# USB_OTG.net
KiCad netlist of a schematic drawn in Altium Designer
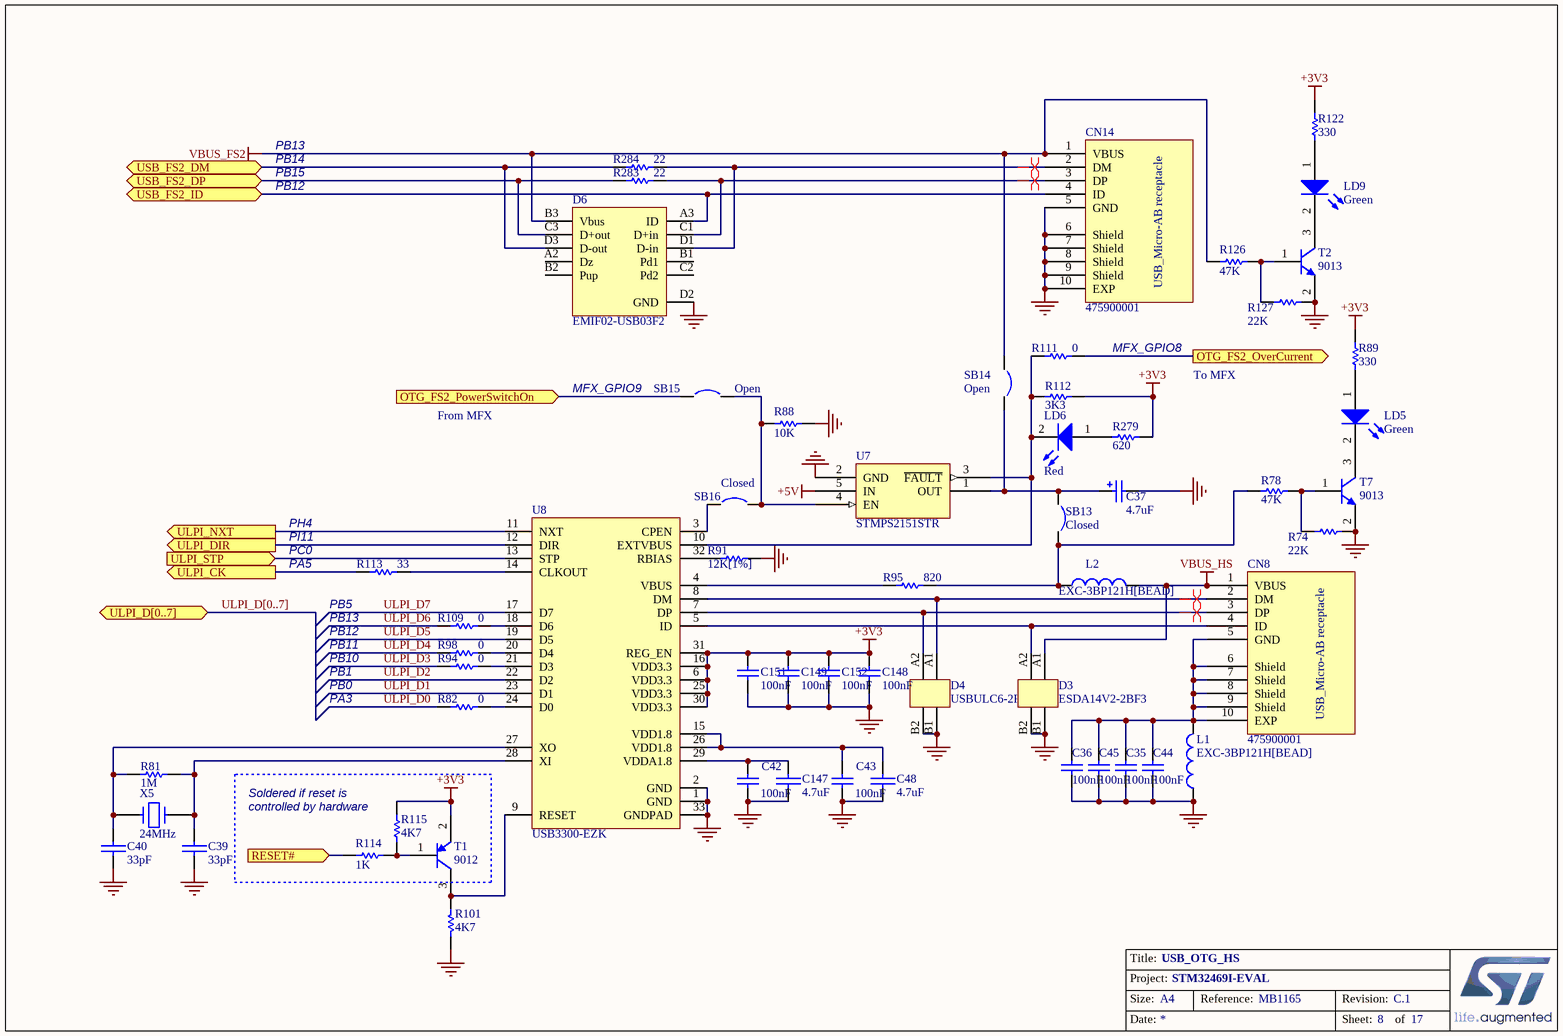
[diagram p0: USB_OTG.SchDoc]

(export (version "E")
  (design (tool "Eeschema 10.0.6"))
  (components
    (comp (ref "C35")
      (value "100nF")
      (footprint "0603C")
      (description "Capacitor")
      (fields (field (name "PUBLISHER") "Altium Limited"))
      (libsource (lib "Miscellaneous Devices") (part "Cap"))
    )
    (comp (ref "C36")
      (value "100nF")
      (footprint "0603C")
      (description "Capacitor")
      (fields (field (name "PUBLISHER") "Altium Limited"))
      (libsource (lib "Miscellaneous Devices") (part "Cap"))
    )
    (comp (ref "C37")
      (value "4.7uF")
      (footprint "TAN-A")
      (description "Polarized Capacitor (Radial)")
      (fields (field (name "PUBLISHER") "Altium Limited"))
      (libsource (lib "Miscellaneous Devices") (part "Cap Pol1"))
    )
    (comp (ref "C39")
      (value "33pF")
      (footprint "0603C")
      (description "Capacitor")
      (libsource (lib "") (part "CAP_1"))
    )
    (comp (ref "C40")
      (value "33pF")
      (footprint "0603C")
      (description "Capacitor")
      (libsource (lib "") (part "CAP_1"))
    )
    (comp (ref "C42")
      (value "100nF")
      (footprint "0603C")
      (description "Capacitor")
      (fields (field (name "PUBLISHER") "Altium Limited"))
      (libsource (lib "Miscellaneous Devices") (part "Cap"))
    )
    (comp (ref "C43")
      (value "100nF")
      (footprint "0603C")
      (description "Capacitor")
      (fields (field (name "PUBLISHER") "Altium Limited"))
      (libsource (lib "Miscellaneous Devices") (part "Cap"))
    )
    (comp (ref "C44")
      (value "100nF")
      (footprint "0603C")
      (description "Capacitor")
      (fields (field (name "PUBLISHER") "Altium Limited"))
      (libsource (lib "Miscellaneous Devices") (part "Cap"))
    )
    (comp (ref "C45")
      (value "100nF")
      (footprint "0603C")
      (description "Capacitor")
      (fields (field (name "PUBLISHER") "Altium Limited"))
      (libsource (lib "Miscellaneous Devices") (part "Cap"))
    )
    (comp (ref "C48")
      (value "4.7uF")
      (footprint "TAN-A")
      (description "Capacitor")
      (libsource (lib "*") (part "CAP"))
    )
    (comp (ref "C147")
      (value "4.7uF")
      (footprint "TAN-A")
      (description "Capacitor")
      (libsource (lib "*") (part "CAP"))
    )
    (comp (ref "C148")
      (value "100nF")
      (footprint "0603C")
      (description "Capacitor")
      (fields (field (name "PUBLISHER") "Altium Limited"))
      (libsource (lib "Miscellaneous Devices") (part "Cap"))
    )
    (comp (ref "C149")
      (value "100nF")
      (footprint "0603C")
      (description "Capacitor")
      (fields (field (name "PUBLISHER") "Altium Limited"))
      (libsource (lib "Miscellaneous Devices") (part "Cap"))
    )
    (comp (ref "C151")
      (value "100nF")
      (footprint "0603C")
      (description "Capacitor")
      (fields (field (name "PUBLISHER") "Altium Limited"))
      (libsource (lib "Miscellaneous Devices") (part "Cap"))
    )
    (comp (ref "C152")
      (value "100nF")
      (footprint "0603C")
      (description "Capacitor")
      (fields (field (name "PUBLISHER") "Altium Limited"))
      (libsource (lib "Miscellaneous Devices") (part "Cap"))
    )
    (comp (ref "CN8")
      (value "475900001")
      (footprint "MOLEX_47590001")
      (libsource (lib "mb1045") (part "475900001"))
    )
    (comp (ref "CN14")
      (value "475900001")
      (footprint "MOLEX_47590001")
      (libsource (lib "mb1045") (part "475900001"))
    )
    (comp (ref "D3")
      (value "ESDA14V2-2BF3")
      (footprint "BGA4_0R4_0R8X0R8")
      (libsource (lib "MB786") (part "ESDA14V2-2BF3"))
    )
    (comp (ref "D4")
      (value "USBULC6-2F3")
      (footprint "BGA4_0R4_1X1")
      (libsource (lib "MB786") (part "USBULC6-2F3"))
    )
    (comp (ref "D6")
      (value "EMIF02-USB03F2")
      (footprint "BGA11_0R5_1R57X2R07")
      (libsource (lib "mb1045") (part "EMIF02-USB03F2"))
    )
    (comp (ref "L1")
      (value "EXC-3BP121H[BEAD]")
      (footprint "0603L")
      (description "Inductor")
      (fields (field (name "PUBLISHER") "Altium Limited"))
      (libsource (lib "Miscellaneous Devices") (part "Inductor"))
    )
    (comp (ref "L2")
      (value "EXC-3BP121H[BEAD]")
      (footprint "0603L")
      (description "Inductor")
      (fields (field (name "PUBLISHER") "Altium Limited"))
      (libsource (lib "Miscellaneous Devices") (part "Inductor"))
    )
    (comp (ref "LD5")
      (value "Green")
      (footprint "0603D")
      (description "Typical RED, GREEN, YELLOW, AMBER GaAs LED")
      (fields (field (name "PUBLISHER") "Altium Limited"))
      (libsource (lib "Miscellaneous Devices") (part "LED2"))
    )
    (comp (ref "LD6")
      (value "Red")
      (footprint "0603D")
      (description "Typical RED, GREEN, YELLOW, AMBER GaAs LED")
      (fields (field (name "PUBLISHER") "Altium Limited"))
      (libsource (lib "Miscellaneous Devices") (part "LED2"))
    )
    (comp (ref "LD9")
      (value "Green")
      (footprint "0603D")
      (description "Typical RED, GREEN, YELLOW, AMBER GaAs LED")
      (fields (field (name "PUBLISHER") "Altium Limited"))
      (libsource (lib "Miscellaneous Devices") (part "LED2"))
    )
    (comp (ref "R74")
      (value "22K")
      (footprint "0603R")
      (description "Resistor")
      (fields (field (name "PUBLISHER") "Altium Limited"))
      (libsource (lib "Miscellaneous Devices") (part "res1"))
    )
    (comp (ref "R78")
      (value "47K")
      (footprint "0603R")
      (description "Resistor")
      (fields (field (name "PUBLISHER") "Altium Limited"))
      (libsource (lib "Miscellaneous Devices") (part "res1"))
    )
    (comp (ref "R81")
      (value "1M")
      (footprint "0603R")
      (description "Resistor")
      (fields (field (name "PUBLISHER") "Altium Limited"))
      (libsource (lib "Miscellaneous Devices") (part "Res1"))
    )
    (comp (ref "R82")
      (value "0")
      (footprint "0603R")
      (description "Resistor")
      (fields (field (name "PUBLISHER") "Altium Limited"))
      (libsource (lib "Miscellaneous Devices") (part "Res1"))
    )
    (comp (ref "R88")
      (value "10K")
      (footprint "0603R")
      (description "Resistor")
      (fields (field (name "PUBLISHER") "Altium Limited"))
      (libsource (lib "Miscellaneous Devices") (part "res1"))
    )
    (comp (ref "R89")
      (value "330")
      (footprint "0603R")
      (description "Resistor")
      (fields (field (name "PUBLISHER") "Altium Limited"))
      (libsource (lib "Miscellaneous Devices") (part "res1"))
    )
    (comp (ref "R91")
      (value "12K[1%]")
      (footprint "0603R")
      (description "Resistor")
      (fields (field (name "PUBLISHER") "Altium Limited"))
      (libsource (lib "Miscellaneous Devices") (part "Res1"))
    )
    (comp (ref "R94")
      (value "0")
      (footprint "0603R")
      (description "Resistor")
      (fields (field (name "PUBLISHER") "Altium Limited"))
      (libsource (lib "Miscellaneous Devices") (part "Res1"))
    )
    (comp (ref "R95")
      (value "820")
      (footprint "0603R")
      (description "Resistor")
      (fields (field (name "PUBLISHER") "Altium Limited"))
      (libsource (lib "Miscellaneous Devices") (part "res1"))
    )
    (comp (ref "R98")
      (value "0")
      (footprint "0603R")
      (description "Resistor")
      (fields (field (name "PUBLISHER") "Altium Limited"))
      (libsource (lib "Miscellaneous Devices") (part "Res1"))
    )
    (comp (ref "R101")
      (value "4K7")
      (footprint "0603R")
      (description "Resistor")
      (fields (field (name "PUBLISHER") "Altium Limited"))
      (libsource (lib "*") (part "Res1"))
    )
    (comp (ref "R109")
      (value "0")
      (footprint "0603R")
      (description "Resistor")
      (fields (field (name "PUBLISHER") "Altium Limited"))
      (libsource (lib "Miscellaneous Devices") (part "Res1"))
    )
    (comp (ref "R111")
      (value "0")
      (footprint "0603R")
      (description "Resistor")
      (fields (field (name "PUBLISHER") "Altium Limited"))
      (libsource (lib "Miscellaneous Devices") (part "Res1"))
    )
    (comp (ref "R112")
      (value "3K3")
      (footprint "0603R")
      (description "Resistor")
      (fields (field (name "PUBLISHER") "Altium Limited"))
      (libsource (lib "Miscellaneous Devices") (part "res1"))
    )
    (comp (ref "R113")
      (value "33")
      (footprint "0603R")
      (description "Resistor")
      (fields (field (name "PUBLISHER") "Altium Limited"))
      (libsource (lib "Miscellaneous Devices") (part "Res1"))
    )
    (comp (ref "R114")
      (value "1K")
      (footprint "0603R")
      (description "Resistor")
      (fields (field (name "PUBLISHER") "Altium Limited"))
      (libsource (lib "Miscellaneous Devices") (part "Res1"))
    )
    (comp (ref "R115")
      (value "4K7")
      (footprint "0603R")
      (description "Resistor")
      (fields (field (name "PUBLISHER") "Altium Limited"))
      (libsource (lib "*") (part "Res1"))
    )
    (comp (ref "R122")
      (value "330")
      (footprint "0603R")
      (description "Resistor")
      (fields (field (name "PUBLISHER") "Altium Limited"))
      (libsource (lib "Miscellaneous Devices") (part "res1"))
    )
    (comp (ref "R126")
      (value "47K")
      (footprint "0603R")
      (description "Resistor")
      (fields (field (name "PUBLISHER") "Altium Limited"))
      (libsource (lib "Miscellaneous Devices") (part "res1"))
    )
    (comp (ref "R127")
      (value "22K")
      (footprint "0603R")
      (description "Resistor")
      (fields (field (name "PUBLISHER") "Altium Limited"))
      (libsource (lib "Miscellaneous Devices") (part "res1"))
    )
    (comp (ref "R279")
      (value "620")
      (footprint "0603R")
      (description "Resistor")
      (fields (field (name "PUBLISHER") "Altium Limited"))
      (libsource (lib "Miscellaneous Devices") (part "Res1"))
    )
    (comp (ref "R283")
      (value "22")
      (footprint "0603R")
      (description "Resistor")
      (fields (field (name "PUBLISHER") "Altium Limited"))
      (libsource (lib "Miscellaneous Devices") (part "Res1"))
    )
    (comp (ref "R284")
      (value "22")
      (footprint "0603R")
      (description "Resistor")
      (fields (field (name "PUBLISHER") "Altium Limited"))
      (libsource (lib "Miscellaneous Devices") (part "Res1"))
    )
    (comp (ref "SB13")
      (value "Closed")
      (footprint "SB_0603")
      (description "Circuit Breaker")
      (fields (field (name "PUBLISHER") "Altium Limited"))
      (libsource (lib "MB1165") (part "Circuit Breaker_close"))
    )
    (comp (ref "SB14")
      (value "Open")
      (footprint "SB_0603")
      (description "Circuit Breaker")
      (fields (field (name "PUBLISHER") "Altium Limited"))
      (libsource (lib "MB1165") (part "Circuit Breaker"))
    )
    (comp (ref "SB15")
      (value "Open")
      (footprint "SB_0603")
      (description "Circuit Breaker")
      (fields (field (name "PUBLISHER") "Altium Limited"))
      (libsource (lib "MB1165") (part "Circuit Breaker"))
    )
    (comp (ref "SB16")
      (value "Closed")
      (footprint "SB_0603")
      (description "Circuit Breaker")
      (fields (field (name "PUBLISHER") "Altium Limited"))
      (libsource (lib "MB1165") (part "Circuit Breaker_close"))
    )
    (comp (ref "T1")
      (value "9012")
      (footprint "SOT-23")
      (description "PNP Bipolar Transistor")
      (fields (field (name "PUBLISHER") "Altium Limited"))
      (libsource (lib "MB1165") (part "PNP"))
    )
    (comp (ref "T2")
      (value "9013")
      (footprint "SOT-23")
      (description "NPN Bipolar Transistor")
      (fields (field (name "PUBLISHER") "Altium Limited"))
      (libsource (lib "MB1167") (part "NPN"))
    )
    (comp (ref "T7")
      (value "9013")
      (footprint "SOT-23")
      (description "NPN Bipolar Transistor")
      (fields (field (name "PUBLISHER") "Altium Limited"))
      (libsource (lib "MB1167") (part "NPN"))
    )
    (comp (ref "U7")
      (value "STMPS2151STR")
      (footprint "SOT23-5")
      (libsource (lib "mb1045") (part "STMPS2141STR"))
    )
    (comp (ref "U8")
      (value "USB3300-EZK")
      (footprint "QFN32_0R5_5X5")
      (libsource (lib "MB1000_1") (part "USB3300-EZK"))
    )
    (comp (ref "X5")
      (value "24MHz")
      (footprint "XTAL1")
      (description "Crystal")
      (libsource (lib "*") (part "CRYSTAL"))
    )
  )
  (nets
    (net (code "1") (name "+3V3") (class "Default")
      (node (ref "C148") (pin "1") (pinfunction "1_1") (pintype "passive"))
      (node (ref "C149") (pin "1") (pinfunction "1_1") (pintype "passive"))
      (node (ref "C151") (pin "1") (pinfunction "1_1") (pintype "passive"))
      (node (ref "C152") (pin "1") (pinfunction "1_1") (pintype "passive"))
      (node (ref "R112") (pin "1") (pinfunction "1_1") (pintype "passive"))
      (node (ref "R115") (pin "1") (pinfunction "1_1") (pintype "passive"))
      (node (ref "R122") (pin "2") (pinfunction "2_2") (pintype "passive"))
      (node (ref "R279") (pin "2") (pinfunction "2_2") (pintype "passive"))
      (node (ref "R89") (pin "2") (pinfunction "2_2") (pintype "passive"))
      (node (ref "T1") (pin "2") (pinfunction "E_2") (pintype "passive"))
      (node (ref "U8") (pin "16") (pinfunction "VDD3.3_16") (pintype "passive"))
      (node (ref "U8") (pin "25") (pinfunction "VDD3.3_25") (pintype "passive"))
      (node (ref "U8") (pin "30") (pinfunction "VDD3.3_30") (pintype "passive"))
      (node (ref "U8") (pin "31") (pinfunction "REG_EN_31") (pintype "passive"))
      (node (ref "U8") (pin "6") (pinfunction "VDD3.3_6") (pintype "passive"))
    )
    (net (code "2") (name "+5V") (class "Default")
      (node (ref "U7") (pin "5") (pinfunction "IN_5") (pintype "passive"))
    )
    (net (code "3") (name "/OTG_FS2_OverCurrent") (class "Default")
      (node (ref "R111") (pin "1") (pinfunction "1_1") (pintype "passive"))
    )
    (net (code "4") (name "/OTG_FS2_PowerSwitchOn") (class "Default")
      (node (ref "SB15") (pin "1") (pinfunction "1_1") (pintype "passive"))
    )
    (net (code "5") (name "/RESET#") (class "Default")
      (node (ref "R114") (pin "2") (pinfunction "2_2") (pintype "passive"))
    )
    (net (code "6") (name "/ULPI_CK") (class "Default")
      (node (ref "R113") (pin "2") (pinfunction "2_2") (pintype "passive"))
    )
    (net (code "7") (name "/ULPI_D0") (class "Default")
      (node (ref "R82") (pin "2") (pinfunction "2_2") (pintype "passive"))
    )
    (net (code "8") (name "/ULPI_D1") (class "Default")
      (node (ref "U8") (pin "23") (pinfunction "D1_23") (pintype "passive"))
    )
    (net (code "9") (name "/ULPI_D2") (class "Default")
      (node (ref "U8") (pin "22") (pinfunction "D2_22") (pintype "passive"))
    )
    (net (code "10") (name "/ULPI_D3") (class "Default")
      (node (ref "R94") (pin "2") (pinfunction "2_2") (pintype "passive"))
    )
    (net (code "11") (name "/ULPI_D4") (class "Default")
      (node (ref "R98") (pin "2") (pinfunction "2_2") (pintype "passive"))
    )
    (net (code "12") (name "/ULPI_D5") (class "Default")
      (node (ref "U8") (pin "19") (pinfunction "D5_19") (pintype "passive"))
    )
    (net (code "13") (name "/ULPI_D6") (class "Default")
      (node (ref "R109") (pin "2") (pinfunction "2_2") (pintype "passive"))
    )
    (net (code "14") (name "/ULPI_D7") (class "Default")
      (node (ref "U8") (pin "17") (pinfunction "D7_17") (pintype "passive"))
    )
    (net (code "15") (name "/ULPI_DIR") (class "Default")
      (node (ref "U8") (pin "12") (pinfunction "DIR_12") (pintype "passive"))
    )
    (net (code "17") (name "/ULPI_NXT") (class "Default")
      (node (ref "U8") (pin "11") (pinfunction "NXT_11") (pintype "passive"))
    )
    (net (code "18") (name "/ULPI_STP") (class "Default")
      (node (ref "U8") (pin "13") (pinfunction "STP_13") (pintype "passive"))
    )
    (net (code "19") (name "/USB_FS2_DM") (class "Default")
      (node (ref "D6") (pin "D3") (pinfunction "D-out_D3") (pintype "passive"))
      (node (ref "R284") (pin "2") (pinfunction "2_2") (pintype "passive"))
    )
    (net (code "20") (name "/USB_FS2_DP") (class "Default")
      (node (ref "D6") (pin "C3") (pinfunction "D+out_C3") (pintype "passive"))
      (node (ref "R283") (pin "2") (pinfunction "2_2") (pintype "passive"))
    )
    (net (code "21") (name "/USB_FS2_ID") (class "Default")
      (node (ref "CN14") (pin "4") (pinfunction "ID_4") (pintype "passive"))
      (node (ref "D6") (pin "A3") (pinfunction "ID_A3") (pintype "passive"))
    )
    (net (code "22") (name "GND") (class "Default")
      (node (ref "C147") (pin "2") (pinfunction "2_2") (pintype "passive"))
      (node (ref "C148") (pin "2") (pinfunction "2_2") (pintype "passive"))
      (node (ref "C149") (pin "2") (pinfunction "2_2") (pintype "passive"))
      (node (ref "C151") (pin "2") (pinfunction "2_2") (pintype "passive"))
      (node (ref "C152") (pin "2") (pinfunction "2_2") (pintype "passive"))
      (node (ref "C35") (pin "2") (pinfunction "2_2") (pintype "passive"))
      (node (ref "C36") (pin "2") (pinfunction "2_2") (pintype "passive"))
      (node (ref "C37") (pin "2") (pinfunction "2_2") (pintype "passive"))
      (node (ref "C39") (pin "2") (pinfunction "2_2") (pintype "passive"))
      (node (ref "C40") (pin "2") (pinfunction "2_2") (pintype "passive"))
      (node (ref "C42") (pin "2") (pinfunction "2_2") (pintype "passive"))
      (node (ref "C43") (pin "2") (pinfunction "2_2") (pintype "passive"))
      (node (ref "C44") (pin "2") (pinfunction "2_2") (pintype "passive"))
      (node (ref "C45") (pin "2") (pinfunction "2_2") (pintype "passive"))
      (node (ref "C48") (pin "2") (pinfunction "2_2") (pintype "passive"))
      (node (ref "CN14") (pin "10") (pinfunction "EXP_10") (pintype "passive"))
      (node (ref "CN14") (pin "5") (pinfunction "GND_5") (pintype "passive"))
      (node (ref "CN14") (pin "6") (pinfunction "Shield_6") (pintype "passive"))
      (node (ref "CN14") (pin "7") (pinfunction "Shield_7") (pintype "passive"))
      (node (ref "CN14") (pin "8") (pinfunction "Shield_8") (pintype "passive"))
      (node (ref "CN14") (pin "9") (pinfunction "Shield_9") (pintype "passive"))
      (node (ref "D3") (pin "B1") (pintype "passive"))
      (node (ref "D3") (pin "B2") (pintype "passive"))
      (node (ref "D4") (pin "B1") (pintype "passive"))
      (node (ref "D4") (pin "B2") (pintype "passive"))
      (node (ref "D6") (pin "D2") (pinfunction "GND_D2") (pintype "passive"))
      (node (ref "L1") (pin "1") (pinfunction "1_1") (pintype "passive"))
      (node (ref "R101") (pin "1") (pinfunction "1_1") (pintype "passive"))
      (node (ref "R127") (pin "1") (pinfunction "1_1") (pintype "passive"))
      (node (ref "R74") (pin "1") (pinfunction "1_1") (pintype "passive"))
      (node (ref "R88") (pin "1") (pinfunction "1_1") (pintype "passive"))
      (node (ref "R91") (pin "1") (pinfunction "1_1") (pintype "passive"))
      (node (ref "T2") (pin "2") (pinfunction "E_2") (pintype "passive"))
      (node (ref "T7") (pin "2") (pinfunction "E_2") (pintype "passive"))
      (node (ref "U7") (pin "2") (pinfunction "GND_2") (pintype "passive"))
      (node (ref "U8") (pin "1") (pinfunction "GND_1") (pintype "passive"))
      (node (ref "U8") (pin "2") (pinfunction "GND_2") (pintype "passive"))
      (node (ref "U8") (pin "33") (pinfunction "GNDPAD_33") (pintype "passive"))
    )
    (net (code "23") (name "Net-(C43-Pad1)") (class "Default")
      (node (ref "C43") (pin "1") (pinfunction "1_1") (pintype "passive"))
      (node (ref "C48") (pin "1") (pinfunction "1_1") (pintype "passive"))
      (node (ref "U8") (pin "15") (pinfunction "VDD1.8_15") (pintype "passive"))
      (node (ref "U8") (pin "26") (pinfunction "VDD1.8_26") (pintype "passive"))
    )
    (net (code "24") (name "Net-(CN8-DM)") (class "Default")
      (node (ref "CN8") (pin "2") (pinfunction "DM_2") (pintype "passive"))
      (node (ref "D4") (pin "A1") (pintype "passive"))
      (node (ref "U8") (pin "8") (pinfunction "DM_8") (pintype "passive"))
    )
    (net (code "25") (name "Net-(CN8-DP)") (class "Default")
      (node (ref "CN8") (pin "3") (pinfunction "DP_3") (pintype "passive"))
      (node (ref "D4") (pin "A2") (pintype "passive"))
      (node (ref "U8") (pin "7") (pinfunction "DP_7") (pintype "passive"))
    )
    (net (code "26") (name "Net-(CN8-EXP)") (class "Default")
      (node (ref "C35") (pin "1") (pinfunction "1_1") (pintype "passive"))
      (node (ref "C36") (pin "1") (pinfunction "1_1") (pintype "passive"))
      (node (ref "C44") (pin "1") (pinfunction "1_1") (pintype "passive"))
      (node (ref "C45") (pin "1") (pinfunction "1_1") (pintype "passive"))
      (node (ref "CN8") (pin "10") (pinfunction "EXP_10") (pintype "passive"))
      (node (ref "CN8") (pin "5") (pinfunction "GND_5") (pintype "passive"))
      (node (ref "CN8") (pin "6") (pinfunction "Shield_6") (pintype "passive"))
      (node (ref "CN8") (pin "7") (pinfunction "Shield_7") (pintype "passive"))
      (node (ref "CN8") (pin "8") (pinfunction "Shield_8") (pintype "passive"))
      (node (ref "CN8") (pin "9") (pinfunction "Shield_9") (pintype "passive"))
      (node (ref "L1") (pin "2") (pinfunction "2_2") (pintype "passive"))
    )
    (net (code "27") (name "Net-(CN8-ID)") (class "Default")
      (node (ref "CN8") (pin "4") (pinfunction "ID_4") (pintype "passive"))
      (node (ref "D3") (pin "A2") (pintype "passive"))
      (node (ref "U8") (pin "5") (pinfunction "ID_5") (pintype "passive"))
    )
    (net (code "28") (name "Net-(CN14-DM)") (class "Default")
      (node (ref "CN14") (pin "2") (pinfunction "DM_2") (pintype "passive"))
      (node (ref "D6") (pin "D1") (pinfunction "D-in_D1") (pintype "passive"))
      (node (ref "R284") (pin "1") (pinfunction "1_1") (pintype "passive"))
    )
    (net (code "29") (name "Net-(CN14-DP)") (class "Default")
      (node (ref "CN14") (pin "3") (pinfunction "DP_3") (pintype "passive"))
      (node (ref "D6") (pin "C1") (pinfunction "D+in_C1") (pintype "passive"))
      (node (ref "R283") (pin "1") (pinfunction "1_1") (pintype "passive"))
    )
    (net (code "30") (name "Net-(L2-Pad1)") (class "Default")
      (node (ref "L2") (pin "1") (pinfunction "1_1") (pintype "passive"))
      (node (ref "R78") (pin "2") (pinfunction "2_2") (pintype "passive"))
      (node (ref "R95") (pin "2") (pinfunction "2_2") (pintype "passive"))
      (node (ref "SB13") (pin "2") (pinfunction "2_2") (pintype "passive"))
    )
    (net (code "31") (name "Net-(LD5-A)") (class "Default")
      (node (ref "LD5") (pin "1") (pinfunction "A_1") (pintype "passive"))
      (node (ref "R89") (pin "1") (pinfunction "1_1") (pintype "passive"))
    )
    (net (code "32") (name "Net-(LD5-K)") (class "Default")
      (node (ref "LD5") (pin "2") (pinfunction "K_2") (pintype "passive"))
      (node (ref "T7") (pin "3") (pinfunction "C_3") (pintype "passive"))
    )
    (net (code "33") (name "Net-(LD6-A)") (class "Default")
      (node (ref "LD6") (pin "1") (pinfunction "A_1") (pintype "passive"))
      (node (ref "R279") (pin "1") (pinfunction "1_1") (pintype "passive"))
    )
    (net (code "34") (name "Net-(LD6-K)") (class "Default")
      (node (ref "LD6") (pin "2") (pinfunction "K_2") (pintype "passive"))
      (node (ref "R111") (pin "2") (pinfunction "2_2") (pintype "passive"))
      (node (ref "R112") (pin "2") (pinfunction "2_2") (pintype "passive"))
      (node (ref "U7") (pin "3") (pinfunction "~{FAULT}_3") (pintype "output"))
      (node (ref "U8") (pin "10") (pinfunction "EXTVBUS_10") (pintype "passive"))
    )
    (net (code "35") (name "Net-(LD9-A)") (class "Default")
      (node (ref "LD9") (pin "1") (pinfunction "A_1") (pintype "passive"))
      (node (ref "R122") (pin "1") (pinfunction "1_1") (pintype "passive"))
    )
    (net (code "36") (name "Net-(LD9-K)") (class "Default")
      (node (ref "LD9") (pin "2") (pinfunction "K_2") (pintype "passive"))
      (node (ref "T2") (pin "3") (pinfunction "C_3") (pintype "passive"))
    )
    (net (code "37") (name "Net-(T1-B)") (class "Default")
      (node (ref "R114") (pin "1") (pinfunction "1_1") (pintype "passive"))
      (node (ref "R115") (pin "2") (pinfunction "2_2") (pintype "passive"))
      (node (ref "T1") (pin "1") (pinfunction "B_1") (pintype "passive"))
    )
    (net (code "38") (name "Net-(T1-C)") (class "Default")
      (node (ref "R101") (pin "2") (pinfunction "2_2") (pintype "passive"))
      (node (ref "T1") (pin "3") (pinfunction "C_3") (pintype "passive"))
      (node (ref "U8") (pin "9") (pinfunction "RESET_9") (pintype "passive"))
    )
    (net (code "39") (name "Net-(T2-B)") (class "Default")
      (node (ref "R126") (pin "2") (pinfunction "2_2") (pintype "passive"))
      (node (ref "R127") (pin "2") (pinfunction "2_2") (pintype "passive"))
      (node (ref "T2") (pin "1") (pinfunction "B_1") (pintype "passive"))
    )
    (net (code "40") (name "Net-(T7-B)") (class "Default")
      (node (ref "R74") (pin "2") (pinfunction "2_2") (pintype "passive"))
      (node (ref "R78") (pin "1") (pinfunction "1_1") (pintype "passive"))
      (node (ref "T7") (pin "1") (pinfunction "B_1") (pintype "passive"))
    )
    (net (code "41") (name "Net-(U7-EN)") (class "Default")
      (node (ref "R88") (pin "2") (pinfunction "2_2") (pintype "passive"))
      (node (ref "SB15") (pin "2") (pinfunction "2_2") (pintype "passive"))
      (node (ref "SB16") (pin "2") (pinfunction "2_2") (pintype "passive"))
      (node (ref "U7") (pin "4") (pinfunction "EN_4") (pintype "input"))
    )
    (net (code "42") (name "Net-(U7-OUT)") (class "Default")
      (node (ref "C37") (pin "1") (pinfunction "1_1") (pintype "passive"))
      (node (ref "SB13") (pin "1") (pinfunction "1_1") (pintype "passive"))
      (node (ref "SB14") (pin "2") (pinfunction "2_2") (pintype "passive"))
      (node (ref "U7") (pin "1") (pinfunction "OUT_1") (pintype "passive"))
    )
    (net (code "43") (name "Net-(U8-CLKOUT)") (class "Default")
      (node (ref "R113") (pin "1") (pinfunction "1_1") (pintype "passive"))
      (node (ref "U8") (pin "14") (pinfunction "CLKOUT_14") (pintype "passive"))
    )
    (net (code "44") (name "Net-(U8-CPEN)") (class "Default")
      (node (ref "SB16") (pin "1") (pinfunction "1_1") (pintype "passive"))
      (node (ref "U8") (pin "3") (pinfunction "CPEN_3") (pintype "passive"))
    )
    (net (code "45") (name "Net-(U8-D0)") (class "Default")
      (node (ref "R82") (pin "1") (pinfunction "1_1") (pintype "passive"))
      (node (ref "U8") (pin "24") (pinfunction "D0_24") (pintype "passive"))
    )
    (net (code "46") (name "Net-(U8-D3)") (class "Default")
      (node (ref "R94") (pin "1") (pinfunction "1_1") (pintype "passive"))
      (node (ref "U8") (pin "21") (pinfunction "D3_21") (pintype "passive"))
    )
    (net (code "47") (name "Net-(U8-D4)") (class "Default")
      (node (ref "R98") (pin "1") (pinfunction "1_1") (pintype "passive"))
      (node (ref "U8") (pin "20") (pinfunction "D4_20") (pintype "passive"))
    )
    (net (code "48") (name "Net-(U8-D6)") (class "Default")
      (node (ref "R109") (pin "1") (pinfunction "1_1") (pintype "passive"))
      (node (ref "U8") (pin "18") (pinfunction "D6_18") (pintype "passive"))
    )
    (net (code "49") (name "Net-(U8-RBIAS)") (class "Default")
      (node (ref "R91") (pin "2") (pinfunction "2_2") (pintype "passive"))
      (node (ref "U8") (pin "32") (pinfunction "RBIAS_32") (pintype "passive"))
    )
    (net (code "50") (name "Net-(U8-VBUS)") (class "Default")
      (node (ref "R95") (pin "1") (pinfunction "1_1") (pintype "passive"))
      (node (ref "U8") (pin "4") (pinfunction "VBUS_4") (pintype "passive"))
    )
    (net (code "51") (name "Net-(U8-VDDA1.8)") (class "Default")
      (node (ref "C147") (pin "1") (pinfunction "1_1") (pintype "passive"))
      (node (ref "C42") (pin "1") (pinfunction "1_1") (pintype "passive"))
      (node (ref "U8") (pin "29") (pinfunction "VDDA1.8_29") (pintype "passive"))
    )
    (net (code "52") (name "Net-(U8-XI)") (class "Default")
      (node (ref "C39") (pin "1") (pinfunction "1_1") (pintype "passive"))
      (node (ref "R81") (pin "2") (pinfunction "2_2") (pintype "passive"))
      (node (ref "U8") (pin "28") (pinfunction "XI_28") (pintype "passive"))
      (node (ref "X5") (pin "1") (pinfunction "1_1") (pintype "passive"))
    )
    (net (code "53") (name "Net-(U8-XO)") (class "Default")
      (node (ref "C40") (pin "1") (pinfunction "1_1") (pintype "passive"))
      (node (ref "R81") (pin "1") (pinfunction "1_1") (pintype "passive"))
      (node (ref "U8") (pin "27") (pinfunction "XO_27") (pintype "passive"))
      (node (ref "X5") (pin "2") (pinfunction "2_2") (pintype "passive"))
    )
    (net (code "54") (name "VBUS_FS2") (class "Default")
      (node (ref "CN14") (pin "1") (pinfunction "VBUS_1") (pintype "passive"))
      (node (ref "D6") (pin "B3") (pinfunction "Vbus_B3") (pintype "passive"))
      (node (ref "R126") (pin "1") (pinfunction "1_1") (pintype "passive"))
      (node (ref "SB14") (pin "1") (pinfunction "1_1") (pintype "passive"))
    )
    (net (code "55") (name "VBUS_HS") (class "Default")
      (node (ref "CN8") (pin "1") (pinfunction "VBUS_1") (pintype "passive"))
      (node (ref "D3") (pin "A1") (pintype "passive"))
      (node (ref "L2") (pin "2") (pinfunction "2_2") (pintype "passive"))
    )
    (net (code "56") (name "unconnected-(D6-Dz-PadA2)") (class "Default")
      (node (ref "D6") (pin "A2") (pinfunction "Dz_A2") (pintype "passive"))
    )
    (net (code "57") (name "unconnected-(D6-Pd1-PadB1)") (class "Default")
      (node (ref "D6") (pin "B1") (pinfunction "Pd1_B1") (pintype "passive"))
    )
    (net (code "58") (name "unconnected-(D6-Pd2-PadC2)") (class "Default")
      (node (ref "D6") (pin "C2") (pinfunction "Pd2_C2") (pintype "passive"))
    )
    (net (code "59") (name "unconnected-(D6-Pup-PadB2)") (class "Default")
      (node (ref "D6") (pin "B2") (pinfunction "Pup_B2") (pintype "passive"))
    )
  )
)
